# AD8310.net
KiCad netlist of a schematic drawn in Altium Designer
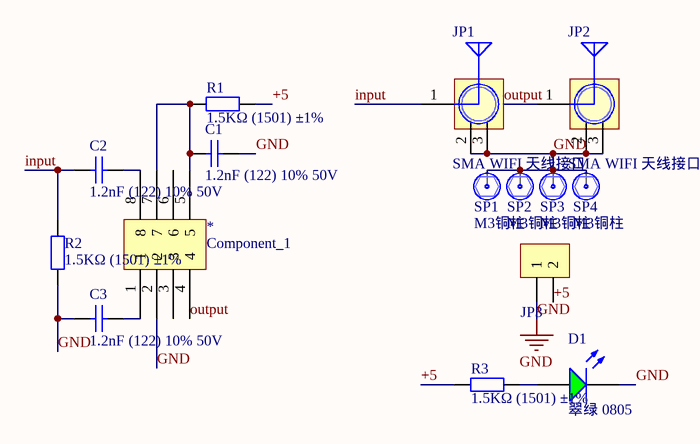
[diagram p0: AD8310峰值检测.SchDoc]

(export (version "E")
  (design (tool "Eeschema 10.0.6"))
  (components
    (comp (ref "*")
      (value "Component_1")
      (footprint "MSOP8_N")
      (libsource (lib "Schlib1") (part "Component_1"))
    )
    (comp (ref "C1")
      (value "1.2nF (122) 10% 50V")
      (footprint "0603_C")
      (description "贴片电容")
      (libsource (lib "Miscellaneous Devices LC") (part "0603 1.2nF (122) 10% 50V"))
    )
    (comp (ref "C2")
      (value "1.2nF (122) 10% 50V")
      (footprint "0603_C")
      (description "贴片电容")
      (libsource (lib "Miscellaneous Devices LC") (part "0603 1.2nF (122) 10% 50V"))
    )
    (comp (ref "C3")
      (value "1.2nF (122) 10% 50V")
      (footprint "0603_C")
      (description "贴片电容")
      (libsource (lib "Miscellaneous Devices LC") (part "0603 1.2nF (122) 10% 50V"))
    )
    (comp (ref "D1")
      (value "翠绿 0805")
      (footprint "0805_LED_S1")
      (description "发光二极管")
      (libsource (lib "Miscellaneous Devices LC") (part "0805 翠绿"))
    )
    (comp (ref "JP1")
      (value "SMA WIFI 天线接口")
      (footprint "SMA-KE")
      (description "SMA-2.4G射频天线接口")
      (libsource (lib "天线") (part "SMA"))
    )
    (comp (ref "JP2")
      (value "SMA WIFI 天线接口")
      (footprint "SMA-KE")
      (description "SMA-2.4G射频天线接口")
      (libsource (lib "天线") (part "SMA"))
    )
    (comp (ref "JP3")
      (value "HDR-1X2")
      (footprint "XH2.54-LI-2P")
      (description "2P接插件")
      (libsource (lib "XH2.54") (part "Header 2"))
    )
    (comp (ref "R1")
      (value "1.5KΩ (1501) ±1%")
      (footprint "0603_R")
      (description "贴片电阻")
      (libsource (lib "Miscellaneous Devices LC") (part "0603 1.5KΩ (1501) 1%"))
    )
    (comp (ref "R2")
      (value "1.5KΩ (1501) ±1%")
      (footprint "0603_R")
      (description "贴片电阻")
      (libsource (lib "") (part "0603 1.5KΩ (1501) 1%_1"))
    )
    (comp (ref "R3")
      (value "1.5KΩ (1501) ±1%")
      (footprint "0603_R")
      (description "贴片电阻")
      (libsource (lib "Miscellaneous Devices LC") (part "0603 1.5KΩ (1501) 1%"))
    )
    (comp (ref "SP1")
      (value "M3铜柱")
      (footprint "M3x4_L")
      (description "铜柱")
      (libsource (lib "铜柱-测试点-电池座-蜂鸣器") (part "铜柱小焊盘"))
    )
    (comp (ref "SP2")
      (value "M3铜柱")
      (footprint "M3x4_L")
      (description "铜柱")
      (libsource (lib "铜柱-测试点-电池座-蜂鸣器") (part "铜柱小焊盘"))
    )
    (comp (ref "SP3")
      (value "M3铜柱")
      (footprint "M3x4_L")
      (description "铜柱")
      (libsource (lib "铜柱-测试点-电池座-蜂鸣器") (part "铜柱小焊盘"))
    )
    (comp (ref "SP4")
      (value "M3铜柱")
      (footprint "M3x4_L")
      (description "铜柱")
      (libsource (lib "铜柱-测试点-电池座-蜂鸣器") (part "铜柱小焊盘"))
    )
  )
  (nets
    (net (code "1") (name "/+5") (class "Default")
      (node (ref "JP3") (pin "2") (pinfunction "2_2") (pintype "passive"))
      (node (ref "R1") (pin "2") (pinfunction "2_2") (pintype "passive"))
      (node (ref "R3") (pin "1") (pinfunction "1_1") (pintype "passive"))
    )
    (net (code "2") (name "/input") (class "Default")
      (node (ref "C2") (pin "1") (pinfunction "1_1") (pintype "passive"))
      (node (ref "JP1") (pin "1") (pinfunction "ANT_1") (pintype "passive"))
      (node (ref "R2") (pin "2") (pinfunction "2_2") (pintype "passive"))
    )
    (net (code "3") (name "/output") (class "Default")
      (node (ref "*") (pin "4") (pinfunction "4_4") (pintype "passive"))
      (node (ref "JP2") (pin "1") (pinfunction "ANT_1") (pintype "passive"))
    )
    (net (code "4") (name "GND") (class "Default")
      (node (ref "*") (pin "2") (pinfunction "2_2") (pintype "passive"))
      (node (ref "C1") (pin "2") (pinfunction "2_2") (pintype "passive"))
      (node (ref "C3") (pin "1") (pinfunction "1_1") (pintype "passive"))
      (node (ref "D1") (pin "K") (pinfunction "K_K") (pintype "passive"))
      (node (ref "JP1") (pin "2") (pinfunction "GND_2") (pintype "passive"))
      (node (ref "JP1") (pin "3") (pinfunction "GND_3") (pintype "passive"))
      (node (ref "JP2") (pin "2") (pinfunction "GND_2") (pintype "passive"))
      (node (ref "JP2") (pin "3") (pinfunction "GND_3") (pintype "passive"))
      (node (ref "JP3") (pin "1") (pinfunction "1_1") (pintype "passive"))
      (node (ref "R2") (pin "1") (pinfunction "1_1") (pintype "passive"))
      (node (ref "SP1") (pin "1") (pinfunction "1_1") (pintype "passive"))
      (node (ref "SP2") (pin "1") (pinfunction "1_1") (pintype "passive"))
      (node (ref "SP3") (pin "1") (pinfunction "1_1") (pintype "passive"))
      (node (ref "SP4") (pin "1") (pinfunction "1_1") (pintype "passive"))
    )
    (net (code "5") (name "Net-(*-Pad1)") (class "Default")
      (node (ref "*") (pin "1") (pinfunction "1_1") (pintype "passive"))
      (node (ref "C3") (pin "2") (pinfunction "2_2") (pintype "passive"))
    )
    (net (code "6") (name "Net-(*-Pad5)") (class "Default")
      (node (ref "*") (pin "5") (pinfunction "5_5") (pintype "passive"))
      (node (ref "*") (pin "7") (pinfunction "7_7") (pintype "passive"))
      (node (ref "C1") (pin "1") (pinfunction "1_1") (pintype "passive"))
      (node (ref "R1") (pin "1") (pinfunction "1_1") (pintype "passive"))
    )
    (net (code "7") (name "Net-(*-Pad8)") (class "Default")
      (node (ref "*") (pin "8") (pinfunction "8_8") (pintype "passive"))
      (node (ref "C2") (pin "2") (pinfunction "2_2") (pintype "passive"))
    )
    (net (code "8") (name "Net-(D1-PadA)") (class "Default")
      (node (ref "D1") (pin "A") (pinfunction "A_A") (pintype "passive"))
      (node (ref "R3") (pin "2") (pinfunction "2_2") (pintype "passive"))
    )
    (net (code "9") (name "unconnected-(*-Pad3)") (class "Default")
      (node (ref "*") (pin "3") (pinfunction "3_3") (pintype "passive"))
    )
    (net (code "10") (name "unconnected-(*-Pad6)") (class "Default")
      (node (ref "*") (pin "6") (pinfunction "6_6") (pintype "passive"))
    )
  )
)
